# bezkontaktowy_miernik_odleg_o_ci.net
KiCad netlist of a schematic drawn in EAGLE
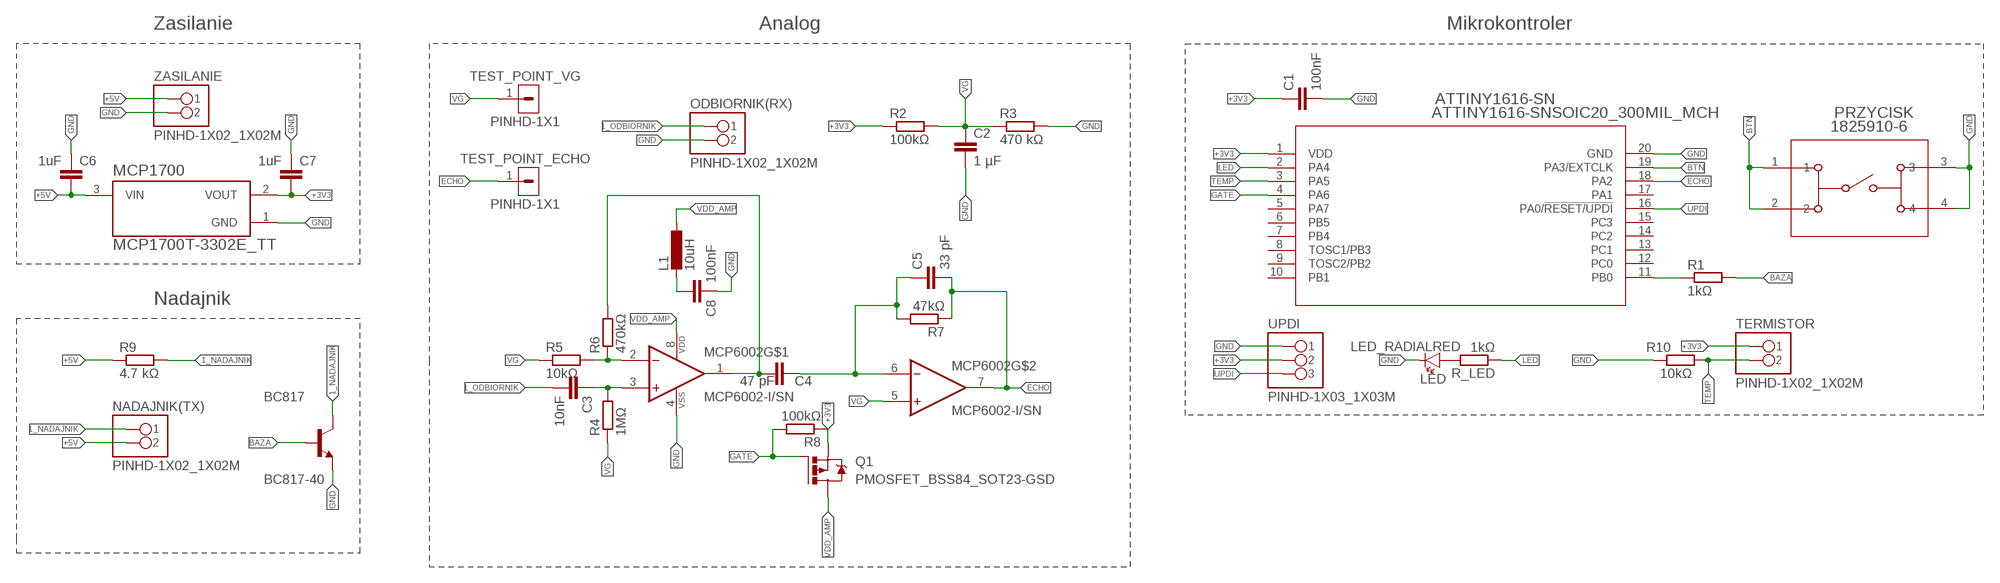
[diagram p0: schematic, sheet 1]

(export (version "E")
  (design (tool "Eeschema 10.0.6"))
  (components
    (comp (ref "ATTINY1616-SN")
      (value "ATTINY1616-SNSOIC20_300MIL_MCH")
      (footprint "eagle-import:SOIC20_300MIL_MCH")
      (fields
        (field (name "MANUFACTURER_PART_NUMBER") "ATTINY1616-SN")
        (field (name "COPYRIGHT") "Copyright (C) 2025 Ultra Librarian. All rights reserved.")
      )
      (libsource (lib "eagle-import") (part "ATTINY1616-SNSOIC20_300MIL_MCH"))
    )
    (comp (ref "BC817")
      (value "BC817-40")
      (footprint "eagle-import:SOT95P240X120-3N")
      (fields (field (name "MANUFACTURER") "Diotec Semiconductor"))
      (libsource (lib "eagle-import") (part "BC817-40"))
    )
    (comp (ref "C1")
      (value "100nF")
      (footprint "eagle-import:C0603")
      (libsource (lib "eagle-import") (part "C-EUC0603"))
    )
    (comp (ref "C2")
      (value "1 µF")
      (footprint "eagle-import:C0603")
      (libsource (lib "eagle-import") (part "C-EUC0603"))
    )
    (comp (ref "C3")
      (value "10nF")
      (footprint "eagle-import:C0603")
      (libsource (lib "eagle-import") (part "C-EUC0603"))
    )
    (comp (ref "C4")
      (value "47 pF")
      (footprint "eagle-import:C0603")
      (libsource (lib "eagle-import") (part "C-EUC0603"))
    )
    (comp (ref "C5")
      (value "33 pF")
      (footprint "eagle-import:C0603")
      (libsource (lib "eagle-import") (part "C-EUC0603"))
    )
    (comp (ref "C6")
      (value "1uF")
      (footprint "eagle-import:C0603")
      (libsource (lib "eagle-import") (part "C-EUC0603"))
    )
    (comp (ref "C7")
      (value "1uF")
      (footprint "eagle-import:C0603")
      (libsource (lib "eagle-import") (part "C-EUC0603"))
    )
    (comp (ref "C8")
      (value "100nF")
      (footprint "eagle-import:C0603")
      (libsource (lib "eagle-import") (part "C-EUC0603"))
    )
    (comp (ref "L1")
      (value "10uH")
      (footprint "eagle-import:0204_7")
      (libsource (lib "eagle-import") (part "L-EU0204/7"))
    )
    (comp (ref "LED")
      (value "LED_RADIALRED")
      (footprint "eagle-import:LEDRD254W60D565H860B_R")
      (libsource (lib "eagle-import") (part "LED_RADIALRED"))
    )
    (comp (ref "MCP1700")
      (value "MCP1700T-3302E_TT")
      (footprint "eagle-import:SOT95P237X112-3N")
      (fields (field (name "MANUFACTURER") "Microchip"))
      (libsource (lib "eagle-import") (part "MCP1700T-3302E_TT"))
    )
    (comp (ref "MCP6002")
      (value "MCP6002-I/SN")
      (footprint "eagle-import:SOIC127P600X175-8N")
      (fields (field (name "MANUFACTURER") "Microchip"))
      (libsource (lib "eagle-import") (part "MCP6002-I/SN"))
    )
    (comp (ref "NADAJNIK(TX)")
      (value "PINHD-1X02_1X02M")
      (footprint "eagle-import:1X02")
      (libsource (lib "eagle-import") (part "PINHD-1X02_1X02M"))
    )
    (comp (ref "ODBIORNIK(RX)")
      (value "PINHD-1X02_1X02M")
      (footprint "eagle-import:1X02")
      (libsource (lib "eagle-import") (part "PINHD-1X02_1X02M"))
    )
    (comp (ref "PRZYCISK")
      (value "1825910-6")
      (footprint "eagle-import:SW4_1825910-B")
      (fields (field (name "COPYRIGHT") "Copyright (C) 2016 Accelerated Designs. All rights reserved"))
      (libsource (lib "eagle-import") (part "1825910-6"))
    )
    (comp (ref "Q1")
      (value "PMOSFET_BSS84_SOT23-GSD")
      (footprint "eagle-import:SOT23")
      (fields (field (name "MANUFACTURER") "onsemi") (field (name "MPN") "BSS84"))
      (libsource (lib "eagle-import") (part "PMOSFET__SOT23-GSDBSS84"))
    )
    (comp (ref "R1")
      (value "1kΩ")
      (footprint "eagle-import:R0603")
      (libsource (lib "eagle-import") (part "R-EU_R0603"))
    )
    (comp (ref "R2")
      (value "100kΩ")
      (footprint "eagle-import:R0603")
      (libsource (lib "eagle-import") (part "R-EU_R0603"))
    )
    (comp (ref "R3")
      (value "470 kΩ")
      (footprint "eagle-import:R0603")
      (libsource (lib "eagle-import") (part "R-EU_R0603"))
    )
    (comp (ref "R4")
      (value "1MΩ")
      (footprint "eagle-import:R0603")
      (libsource (lib "eagle-import") (part "R-EU_R0603"))
    )
    (comp (ref "R5")
      (value "10kΩ")
      (footprint "eagle-import:R0603")
      (libsource (lib "eagle-import") (part "R-EU_R0603"))
    )
    (comp (ref "R6")
      (value "470kΩ")
      (footprint "eagle-import:R0603")
      (libsource (lib "eagle-import") (part "R-EU_R0603"))
    )
    (comp (ref "R7")
      (value "47kΩ")
      (footprint "eagle-import:R0603")
      (libsource (lib "eagle-import") (part "R-EU_R0603"))
    )
    (comp (ref "R8")
      (value "100kΩ")
      (footprint "eagle-import:R0603")
      (libsource (lib "eagle-import") (part "R-EU_R0603"))
    )
    (comp (ref "R9")
      (value "4.7 kΩ")
      (footprint "eagle-import:R0603")
      (libsource (lib "eagle-import") (part "R-EU_R0603"))
    )
    (comp (ref "R10")
      (value "10kΩ")
      (footprint "eagle-import:R0603")
      (libsource (lib "eagle-import") (part "R-EU_R0603"))
    )
    (comp (ref "R_LED")
      (value "1kΩ")
      (footprint "eagle-import:R0603")
      (libsource (lib "eagle-import") (part "R-EU_R0603"))
    )
    (comp (ref "TERMISTOR")
      (value "PINHD-1X02_1X02M")
      (footprint "eagle-import:1X02")
      (libsource (lib "eagle-import") (part "PINHD-1X02_1X02M"))
    )
    (comp (ref "TEST_POINT_ECHO")
      (value "PINHD-1X1")
      (footprint "eagle-import:1X01")
      (libsource (lib "eagle-import") (part "PINHD-1X1"))
    )
    (comp (ref "TEST_POINT_VG")
      (value "PINHD-1X1")
      (footprint "eagle-import:1X01")
      (libsource (lib "eagle-import") (part "PINHD-1X1"))
    )
    (comp (ref "UPDI")
      (value "PINHD-1X03_1X03M")
      (footprint "eagle-import:1X03")
      (libsource (lib "eagle-import") (part "PINHD-1X03_1X03M"))
    )
    (comp (ref "ZASILANIE")
      (value "PINHD-1X02_1X02M")
      (footprint "eagle-import:1X02")
      (libsource (lib "eagle-import") (part "PINHD-1X02_1X02M"))
    )
  )
  (nets
    (net (code "1") (name "+3V3") (class "Default")
      (node (ref "ATTINY1616-SN") (pin "1") (pinfunction "VDD_1") (pintype "power_in"))
      (node (ref "C1") (pin "1") (pinfunction "1_1") (pintype "passive"))
      (node (ref "C7") (pin "2") (pinfunction "2_2") (pintype "passive"))
      (node (ref "MCP1700") (pin "2") (pinfunction "VOUT_2") (pintype "output"))
      (node (ref "Q1") (pin "2") (pinfunction "S_2") (pintype "passive"))
      (node (ref "R2") (pin "1") (pinfunction "1_1") (pintype "passive"))
      (node (ref "R8") (pin "1") (pinfunction "1_1") (pintype "passive"))
      (node (ref "TERMISTOR") (pin "1") (pinfunction "1_1") (pintype "bidirectional"))
      (node (ref "UPDI") (pin "2") (pinfunction "2_2") (pintype "bidirectional"))
    )
    (net (code "2") (name "+5V") (class "Default")
      (node (ref "C6") (pin "2") (pinfunction "2_2") (pintype "passive"))
      (node (ref "MCP1700") (pin "3") (pinfunction "VIN_3") (pintype "input"))
      (node (ref "NADAJNIK(TX)") (pin "2") (pinfunction "2_2") (pintype "bidirectional"))
      (node (ref "R9") (pin "1") (pinfunction "1_1") (pintype "passive"))
      (node (ref "ZASILANIE") (pin "1") (pinfunction "1_1") (pintype "bidirectional"))
    )
    (net (code "3") (name "1_NADAJNIK") (class "Default")
      (node (ref "BC817") (pin "3") (pinfunction "C_3") (pintype "passive"))
      (node (ref "NADAJNIK(TX)") (pin "1") (pinfunction "1_1") (pintype "bidirectional"))
      (node (ref "R9") (pin "2") (pinfunction "2_2") (pintype "passive"))
    )
    (net (code "4") (name "1_ODBIORNIK") (class "Default")
      (node (ref "C3") (pin "2") (pinfunction "2_2") (pintype "passive"))
      (node (ref "ODBIORNIK(RX)") (pin "1") (pinfunction "1_1") (pintype "bidirectional"))
    )
    (net (code "5") (name "BAZA") (class "Default")
      (node (ref "BC817") (pin "1") (pinfunction "B_1") (pintype "passive"))
      (node (ref "R1") (pin "2") (pinfunction "2_2") (pintype "passive"))
    )
    (net (code "6") (name "BTN") (class "Default")
      (node (ref "ATTINY1616-SN") (pin "19") (pinfunction "PA3/EXTCLK_19") (pintype "bidirectional"))
      (node (ref "PRZYCISK") (pin "1") (pinfunction "1_1") (pintype "passive"))
      (node (ref "PRZYCISK") (pin "2") (pinfunction "2_2") (pintype "passive"))
    )
    (net (code "7") (name "ECHO") (class "Default")
      (node (ref "ATTINY1616-SN") (pin "18") (pinfunction "PA2_18") (pintype "bidirectional"))
      (node (ref "C5") (pin "2") (pinfunction "2_2") (pintype "passive"))
      (node (ref "MCP6002") (pin "7") (pinfunction "VOUTB_7") (pintype "output"))
      (node (ref "R7") (pin "1") (pinfunction "1_1") (pintype "passive"))
      (node (ref "TEST_POINT_ECHO") (pin "1") (pinfunction "1_1") (pintype "passive"))
    )
    (net (code "8") (name "GATE") (class "Default")
      (node (ref "ATTINY1616-SN") (pin "4") (pinfunction "PA6_4") (pintype "bidirectional"))
      (node (ref "Q1") (pin "1") (pinfunction "G_1") (pintype "passive"))
      (node (ref "R8") (pin "2") (pinfunction "2_2") (pintype "passive"))
    )
    (net (code "9") (name "GND") (class "Default")
      (node (ref "ATTINY1616-SN") (pin "20") (pinfunction "GND_20") (pintype "passive"))
      (node (ref "BC817") (pin "2") (pinfunction "E_2") (pintype "passive"))
      (node (ref "C1") (pin "2") (pinfunction "2_2") (pintype "passive"))
      (node (ref "C2") (pin "2") (pinfunction "2_2") (pintype "passive"))
      (node (ref "C6") (pin "1") (pinfunction "1_1") (pintype "passive"))
      (node (ref "C7") (pin "1") (pinfunction "1_1") (pintype "passive"))
      (node (ref "C8") (pin "1") (pinfunction "1_1") (pintype "passive"))
      (node (ref "LED") (pin "C") (pinfunction "C_C") (pintype "passive"))
      (node (ref "MCP1700") (pin "1") (pinfunction "GND_1") (pintype "power_in"))
      (node (ref "MCP6002") (pin "4") (pinfunction "VSS_4") (pintype "power_in"))
      (node (ref "ODBIORNIK(RX)") (pin "2") (pinfunction "2_2") (pintype "bidirectional"))
      (node (ref "PRZYCISK") (pin "3") (pinfunction "3_3") (pintype "passive"))
      (node (ref "PRZYCISK") (pin "4") (pinfunction "4_4") (pintype "passive"))
      (node (ref "R10") (pin "1") (pinfunction "1_1") (pintype "passive"))
      (node (ref "R3") (pin "2") (pinfunction "2_2") (pintype "passive"))
      (node (ref "UPDI") (pin "1") (pinfunction "1_1") (pintype "bidirectional"))
      (node (ref "ZASILANIE") (pin "2") (pinfunction "2_2") (pintype "bidirectional"))
    )
    (net (code "10") (name "LED") (class "Default")
      (node (ref "ATTINY1616-SN") (pin "2") (pinfunction "PA4_2") (pintype "bidirectional"))
      (node (ref "R_LED") (pin "1") (pinfunction "1_1") (pintype "passive"))
    )
    (net (code "11") (name "Net-(ATTINY1616-SN-PB0)") (class "Default")
      (node (ref "ATTINY1616-SN") (pin "11") (pinfunction "PB0_11") (pintype "bidirectional"))
      (node (ref "R1") (pin "1") (pinfunction "1_1") (pintype "passive"))
    )
    (net (code "12") (name "Net-(C8-Pad2)") (class "Default")
      (node (ref "C8") (pin "2") (pinfunction "2_2") (pintype "passive"))
      (node (ref "L1") (pin "2") (pinfunction "2_2") (pintype "passive"))
    )
    (net (code "13") (name "Net-(LED-PadA)") (class "Default")
      (node (ref "LED") (pin "A") (pinfunction "A_A") (pintype "passive"))
      (node (ref "R_LED") (pin "2") (pinfunction "2_2") (pintype "passive"))
    )
    (net (code "14") (name "Net-(MCP6002A-VINA+)") (class "Default")
      (node (ref "C3") (pin "1") (pinfunction "1_1") (pintype "passive"))
      (node (ref "MCP6002") (pin "3") (pinfunction "VINA+_3") (pintype "input"))
      (node (ref "R4") (pin "2") (pinfunction "2_2") (pintype "passive"))
    )
    (net (code "15") (name "Net-(MCP6002A-VINA-)") (class "Default")
      (node (ref "MCP6002") (pin "2") (pinfunction "VINA-_2") (pintype "input"))
      (node (ref "R5") (pin "2") (pinfunction "2_2") (pintype "passive"))
      (node (ref "R6") (pin "1") (pinfunction "1_1") (pintype "passive"))
    )
    (net (code "16") (name "Net-(MCP6002A-VOUTA)") (class "Default")
      (node (ref "C4") (pin "2") (pinfunction "2_2") (pintype "passive"))
      (node (ref "MCP6002") (pin "1") (pinfunction "VOUTA_1") (pintype "output"))
      (node (ref "R6") (pin "2") (pinfunction "2_2") (pintype "passive"))
    )
    (net (code "17") (name "Net-(MCP6002B-VINB-)") (class "Default")
      (node (ref "C4") (pin "1") (pinfunction "1_1") (pintype "passive"))
      (node (ref "C5") (pin "1") (pinfunction "1_1") (pintype "passive"))
      (node (ref "MCP6002") (pin "6") (pinfunction "VINB-_6") (pintype "input"))
      (node (ref "R7") (pin "2") (pinfunction "2_2") (pintype "passive"))
    )
    (net (code "18") (name "TEMP") (class "Default")
      (node (ref "ATTINY1616-SN") (pin "3") (pinfunction "PA5_3") (pintype "bidirectional"))
      (node (ref "R10") (pin "2") (pinfunction "2_2") (pintype "passive"))
      (node (ref "TERMISTOR") (pin "2") (pinfunction "2_2") (pintype "bidirectional"))
    )
    (net (code "19") (name "UPDI") (class "Default")
      (node (ref "ATTINY1616-SN") (pin "16") (pinfunction "PA0/~{RESET/UPDI}_16") (pintype "bidirectional"))
      (node (ref "UPDI") (pin "3") (pinfunction "3_3") (pintype "bidirectional"))
    )
    (net (code "20") (name "VDD_AMP") (class "Default")
      (node (ref "L1") (pin "1") (pinfunction "1_1") (pintype "passive"))
      (node (ref "MCP6002") (pin "8") (pinfunction "VDD_8") (pintype "power_in"))
      (node (ref "Q1") (pin "3") (pinfunction "D_3") (pintype "passive"))
    )
    (net (code "21") (name "VG") (class "Default")
      (node (ref "C2") (pin "1") (pinfunction "1_1") (pintype "passive"))
      (node (ref "MCP6002") (pin "5") (pinfunction "VINB+_5") (pintype "input"))
      (node (ref "R2") (pin "2") (pinfunction "2_2") (pintype "passive"))
      (node (ref "R3") (pin "1") (pinfunction "1_1") (pintype "passive"))
      (node (ref "R4") (pin "1") (pinfunction "1_1") (pintype "passive"))
      (node (ref "R5") (pin "1") (pinfunction "1_1") (pintype "passive"))
      (node (ref "TEST_POINT_VG") (pin "1") (pinfunction "1_1") (pintype "passive"))
    )
    (net (code "22") (name "unconnected-(ATTINY1616-SN-PA1-Pad17)") (class "Default")
      (node (ref "ATTINY1616-SN") (pin "17") (pinfunction "PA1_17") (pintype "bidirectional"))
    )
    (net (code "23") (name "unconnected-(ATTINY1616-SN-PA7-Pad5)") (class "Default")
      (node (ref "ATTINY1616-SN") (pin "5") (pinfunction "PA7_5") (pintype "bidirectional"))
    )
    (net (code "24") (name "unconnected-(ATTINY1616-SN-PB1-Pad10)") (class "Default")
      (node (ref "ATTINY1616-SN") (pin "10") (pinfunction "PB1_10") (pintype "bidirectional"))
    )
    (net (code "25") (name "unconnected-(ATTINY1616-SN-PB4-Pad7)") (class "Default")
      (node (ref "ATTINY1616-SN") (pin "7") (pinfunction "PB4_7") (pintype "bidirectional"))
    )
    (net (code "26") (name "unconnected-(ATTINY1616-SN-PB5-Pad6)") (class "Default")
      (node (ref "ATTINY1616-SN") (pin "6") (pinfunction "PB5_6") (pintype "bidirectional"))
    )
    (net (code "27") (name "unconnected-(ATTINY1616-SN-PC0-Pad12)") (class "Default")
      (node (ref "ATTINY1616-SN") (pin "12") (pinfunction "PC0_12") (pintype "bidirectional"))
    )
    (net (code "28") (name "unconnected-(ATTINY1616-SN-PC1-Pad13)") (class "Default")
      (node (ref "ATTINY1616-SN") (pin "13") (pinfunction "PC1_13") (pintype "bidirectional"))
    )
    (net (code "29") (name "unconnected-(ATTINY1616-SN-PC2-Pad14)") (class "Default")
      (node (ref "ATTINY1616-SN") (pin "14") (pinfunction "PC2_14") (pintype "bidirectional"))
    )
    (net (code "30") (name "unconnected-(ATTINY1616-SN-PC3-Pad15)") (class "Default")
      (node (ref "ATTINY1616-SN") (pin "15") (pinfunction "PC3_15") (pintype "bidirectional"))
    )
    (net (code "31") (name "unconnected-(ATTINY1616-SN-TOSC1{slash}PB3-Pad8)") (class "Default")
      (node (ref "ATTINY1616-SN") (pin "8") (pinfunction "TOSC1/PB3_8") (pintype "bidirectional"))
    )
    (net (code "32") (name "unconnected-(ATTINY1616-SN-TOSC2{slash}PB2-Pad9)") (class "Default")
      (node (ref "ATTINY1616-SN") (pin "9") (pinfunction "TOSC2/PB2_9") (pintype "bidirectional"))
    )
  )
)
